# DiffAmpOFS.net
KiCad netlist of a schematic drawn in Altium Designer
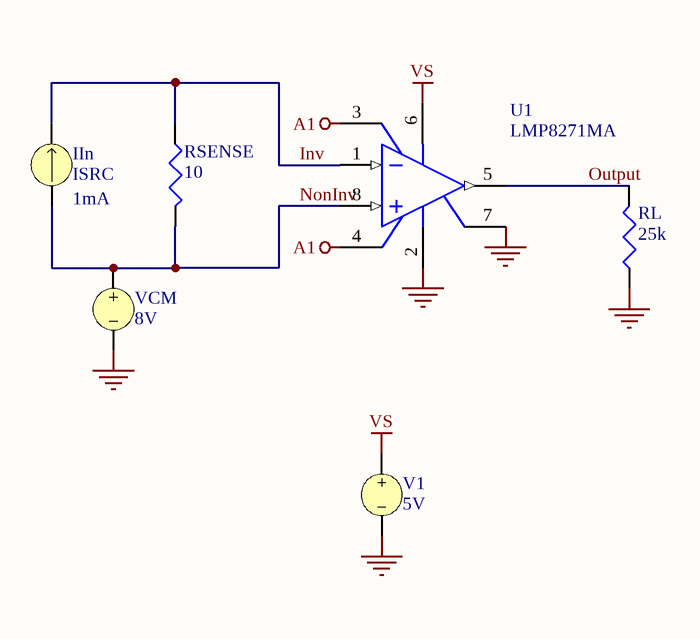
[diagram p0: DiffAmpOFS.schdoc]

(export (version "E")
  (design (tool "Eeschema 10.0.6"))
  (components
    (comp (ref "IIn")
      (value "ISRC")
      (description "Current Source")
      (fields (field (name "AC MAGNITUDE") "1mA") (field (name "PUBLISHER") "Altium Limited"))
      (libsource (lib "Simulation Sources") (part "ISRC"))
    )
    (comp (ref "RL") (value "25k") (description "Resistor") (libsource (lib "") (part "RES_1")))
    (comp (ref "RSENSE")
      (value "10")
      (description "Resistor")
      (fields (field (name "Comment") "10k"))
      (libsource (lib "*") (part "RES"))
    )
    (comp (ref "U1")
      (value "LMP8271MA")
      (footprint "M08A_N")
      (description "High Common Mode, Gain of 20, Bidirectional Precision Voltage Difference Amplifier")
      (fields
        (field (name "MANUFACTURER") "National Semiconductor")
        (field (name "DIGIKEYPARTNUMBER") "LMP8271MA-ND")
        (field (name "PUBLISHER") "Altium Limited")
      )
      (libsource (lib "NSC Amplifier with SIM models") (part "LMP8271MA"))
    )
    (comp (ref "V1")
      (value "5V")
      (description "Voltage Source")
      (fields (field (name "Comment") "12V"))
      (libsource (lib "*") (part "VSRC"))
    )
    (comp (ref "VCM")
      (value "8V")
      (description "Voltage Source")
      (fields (field (name "Comment") "12V"))
      (libsource (lib "*") (part "VSRC"))
    )
  )
  (nets
    (net (code "1") (name "/Inv") (class "Default")
      (node (ref "IIn") (pin "2") (pinfunction "2_2") (pintype "passive"))
      (node (ref "RSENSE") (pin "2") (pinfunction "BOT_2") (pintype "passive"))
      (node (ref "U1") (pin "1") (pinfunction "IN-_1") (pintype "input"))
    )
    (net (code "2") (name "/NonInv") (class "Default")
      (node (ref "IIn") (pin "1") (pinfunction "1_1") (pintype "passive"))
      (node (ref "RSENSE") (pin "1") (pinfunction "TOP_1") (pintype "passive"))
      (node (ref "U1") (pin "8") (pinfunction "IN+_8") (pintype "input"))
      (node (ref "VCM") (pin "1") (pinfunction "1_1") (pintype "passive"))
    )
    (net (code "3") (name "/Output") (class "Default")
      (node (ref "RL") (pin "1") (pinfunction "TOP_1") (pintype "passive"))
      (node (ref "U1") (pin "5") (pinfunction "OUT_5") (pintype "output"))
    )
    (net (code "4") (name "A1") (class "Default")
      (node (ref "U1") (pin "3") (pinfunction "A1_3") (pintype "passive"))
      (node (ref "U1") (pin "4") (pinfunction "A2_4") (pintype "passive"))
    )
    (net (code "5") (name "GND") (class "Default")
      (node (ref "RL") (pin "2") (pinfunction "BOT_2") (pintype "passive"))
      (node (ref "U1") (pin "2") (pinfunction "GND_2") (pintype "power_in"))
      (node (ref "U1") (pin "7") (pinfunction "OFS_7") (pintype "passive"))
      (node (ref "V1") (pin "2") (pinfunction "2_2") (pintype "passive"))
      (node (ref "VCM") (pin "2") (pinfunction "2_2") (pintype "passive"))
    )
    (net (code "6") (name "VS") (class "Default")
      (node (ref "U1") (pin "6") (pinfunction "VS_6") (pintype "power_in"))
      (node (ref "V1") (pin "1") (pinfunction "1_1") (pintype "passive"))
    )
  )
)
